# PW_Connector.net
KiCad netlist of a schematic drawn in EAGLE
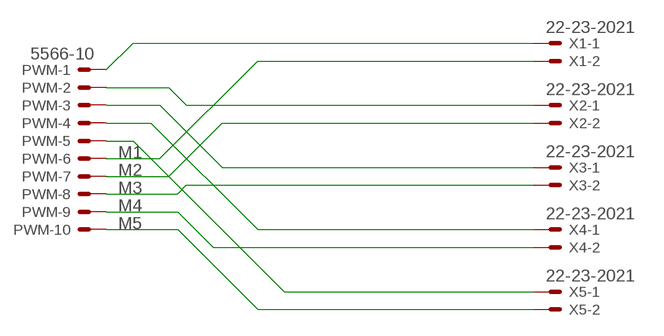
[diagram p0: schematic, sheet 1]

(export (version "E")
  (design (tool "Eeschema 10.0.6"))
  (components
    (comp (ref "PWM")
      (value "5566-10")
      (footprint "eagle-import:5566-10")
      (libsource (lib "eagle-import") (part "5566-10"))
    )
    (comp (ref "X1")
      (value "22-23-2021")
      (footprint "eagle-import:22-23-2021")
      (fields (field (name "MF") "MOLEX"))
      (libsource (lib "eagle-import") (part "22-23-2021"))
    )
    (comp (ref "X2")
      (value "22-23-2021")
      (footprint "eagle-import:22-23-2021")
      (fields (field (name "MF") "MOLEX"))
      (libsource (lib "eagle-import") (part "22-23-2021"))
    )
    (comp (ref "X3")
      (value "22-23-2021")
      (footprint "eagle-import:22-23-2021")
      (fields (field (name "MF") "MOLEX"))
      (libsource (lib "eagle-import") (part "22-23-2021"))
    )
    (comp (ref "X4")
      (value "22-23-2021")
      (footprint "eagle-import:22-23-2021")
      (fields (field (name "MF") "MOLEX"))
      (libsource (lib "eagle-import") (part "22-23-2021"))
    )
    (comp (ref "X5")
      (value "22-23-2021")
      (footprint "eagle-import:22-23-2021")
      (fields (field (name "MF") "MOLEX"))
      (libsource (lib "eagle-import") (part "22-23-2021"))
    )
  )
  (nets
    (net (code "1") (name "/M1") (class "Default")
      (node (ref "PWM") (pin "6") (pinfunction "S_6") (pintype "passive"))
      (node (ref "X1") (pin "2") (pinfunction "S_2") (pintype "passive"))
    )
    (net (code "2") (name "/M2") (class "Default")
      (node (ref "PWM") (pin "7") (pinfunction "S_7") (pintype "passive"))
      (node (ref "X2") (pin "2") (pinfunction "S_2") (pintype "passive"))
    )
    (net (code "3") (name "/M3") (class "Default")
      (node (ref "PWM") (pin "8") (pinfunction "S_8") (pintype "passive"))
      (node (ref "X3") (pin "2") (pinfunction "S_2") (pintype "passive"))
    )
    (net (code "4") (name "/M4") (class "Default")
      (node (ref "PWM") (pin "9") (pinfunction "S_9") (pintype "passive"))
      (node (ref "X4") (pin "2") (pinfunction "S_2") (pintype "passive"))
    )
    (net (code "5") (name "/M5") (class "Default")
      (node (ref "PWM") (pin "10") (pinfunction "S_10") (pintype "passive"))
      (node (ref "X5") (pin "2") (pinfunction "S_2") (pintype "passive"))
    )
    (net (code "6") (name "Net-(PWMA-S)") (class "Default")
      (node (ref "PWM") (pin "1") (pinfunction "S_1") (pintype "passive"))
      (node (ref "X1") (pin "1") (pinfunction "S_1") (pintype "passive"))
    )
    (net (code "7") (name "Net-(PWMC-S)") (class "Default")
      (node (ref "PWM") (pin "2") (pinfunction "S_2") (pintype "passive"))
      (node (ref "X2") (pin "1") (pinfunction "S_1") (pintype "passive"))
    )
    (net (code "8") (name "Net-(PWMD-S)") (class "Default")
      (node (ref "PWM") (pin "3") (pinfunction "S_3") (pintype "passive"))
      (node (ref "X3") (pin "1") (pinfunction "S_1") (pintype "passive"))
    )
    (net (code "9") (name "Net-(PWME-S)") (class "Default")
      (node (ref "PWM") (pin "4") (pinfunction "S_4") (pintype "passive"))
      (node (ref "X4") (pin "1") (pinfunction "S_1") (pintype "passive"))
    )
    (net (code "10") (name "Net-(PWMF-S)") (class "Default")
      (node (ref "PWM") (pin "5") (pinfunction "S_5") (pintype "passive"))
      (node (ref "X5") (pin "1") (pinfunction "S_1") (pintype "passive"))
    )
  )
)
